# i2c-sensor-bridge.net
KiCad netlist of a schematic drawn in EAGLE
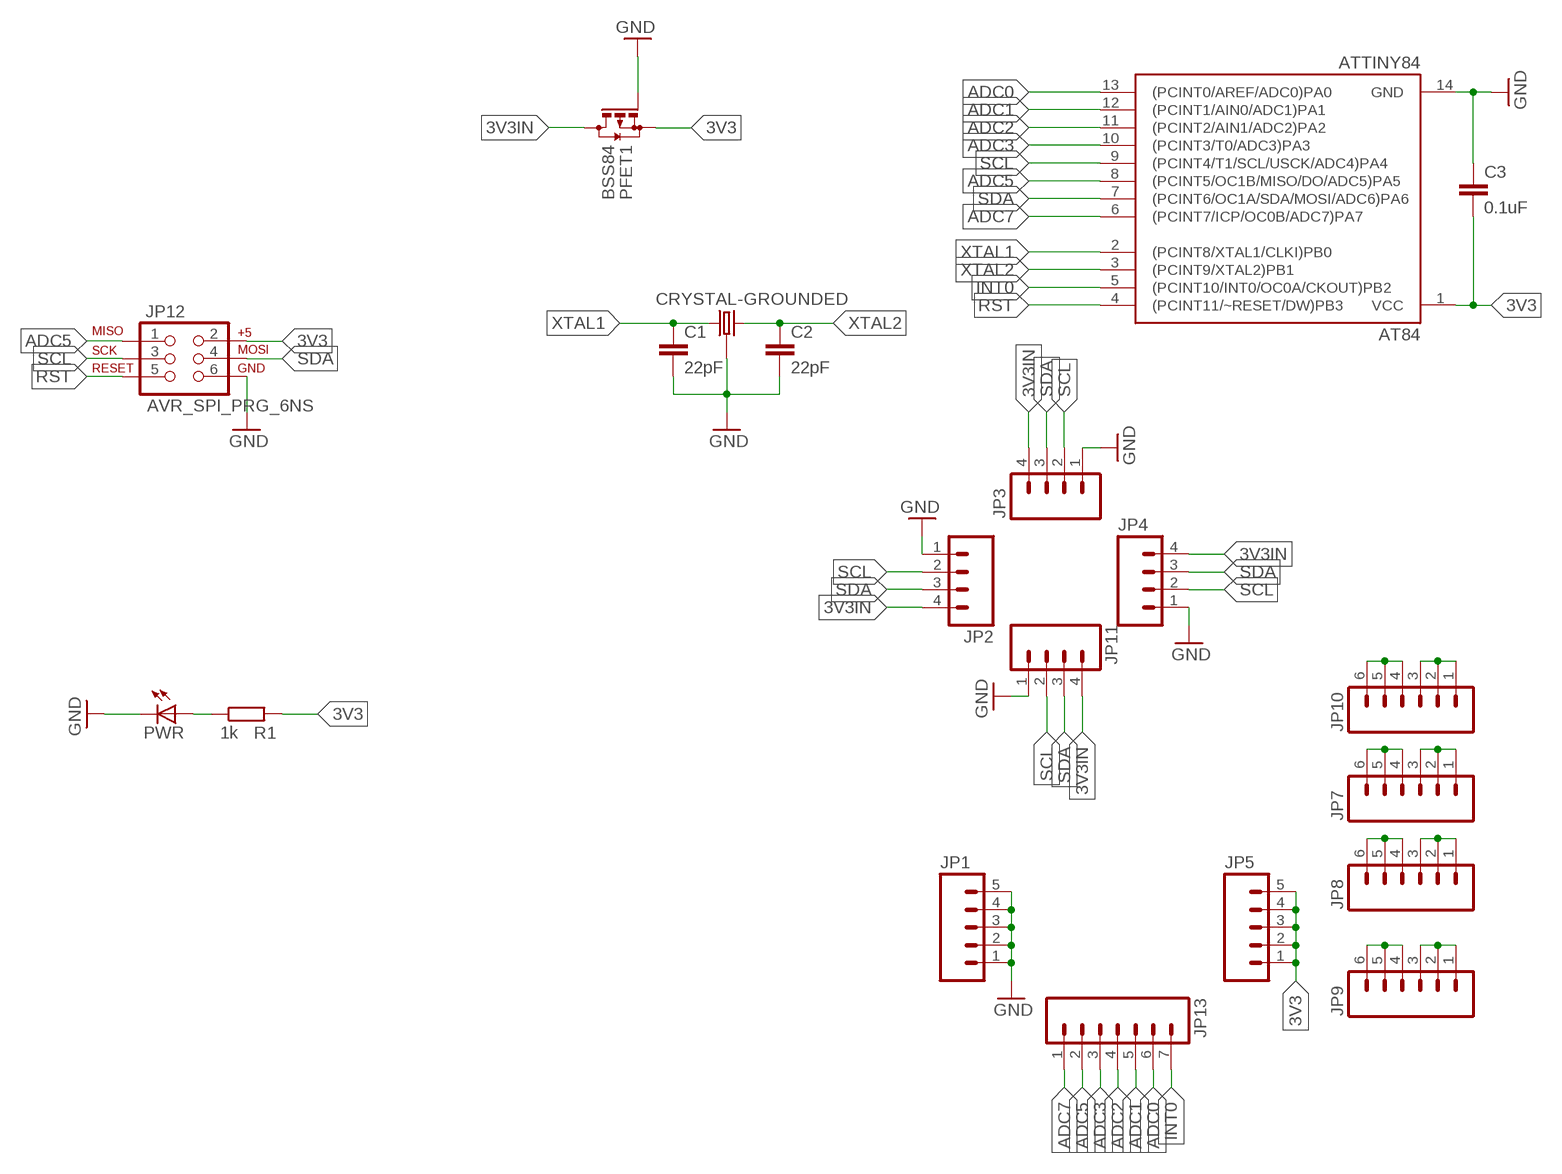
[diagram p0: schematic, sheet 1]

(export (version "E")
  (design (tool "Eeschema 10.0.6"))
  (components
    (comp (ref "AT84")
      (value "ATTINY84")
      (footprint "eagle-import:SO14")
      (libsource (lib "eagle-import") (part "ATTINY84"))
    )
    (comp (ref "C1")
      (value "22pF")
      (footprint "eagle-import:C0805")
      (libsource (lib "eagle-import") (part "C-EUC0805"))
    )
    (comp (ref "C2")
      (value "22pF")
      (footprint "eagle-import:C0805")
      (libsource (lib "eagle-import") (part "C-EUC0805"))
    )
    (comp (ref "C3")
      (value "0.1uF")
      (footprint "eagle-import:C0805")
      (libsource (lib "eagle-import") (part "C-EUC0805"))
    )
    (comp (ref "CRYSTAL")
      (value "CRYSTAL-GROUNDED")
      (footprint "eagle-import:CRYSTAL-SMD-5X3")
      (libsource (lib "eagle-import") (part "CRYSTAL-GROUNDED"))
    )
    (comp (ref "JP1")
      (value "M05LOCK")
      (footprint "eagle-import:1X05_LOCK")
      (libsource (lib "eagle-import") (part "M05LOCK"))
    )
    (comp (ref "JP2")
      (value "M04LOCK")
      (footprint "eagle-import:1X04_LOCK")
      (libsource (lib "eagle-import") (part "M04LOCK"))
    )
    (comp (ref "JP3")
      (value "M04LOCK")
      (footprint "eagle-import:1X04_LOCK")
      (libsource (lib "eagle-import") (part "M04LOCK"))
    )
    (comp (ref "JP4")
      (value "M04LOCK")
      (footprint "eagle-import:1X04_LOCK")
      (libsource (lib "eagle-import") (part "M04LOCK"))
    )
    (comp (ref "JP5")
      (value "M05LOCK")
      (footprint "eagle-import:1X05_LOCK")
      (libsource (lib "eagle-import") (part "M05LOCK"))
    )
    (comp (ref "JP7")
      (value "M06NO_SILK_FEMALE_PTH")
      (footprint "eagle-import:1X06_NO_SILK")
      (libsource (lib "eagle-import") (part "M06NO_SILK_FEMALE_PTH"))
    )
    (comp (ref "JP8")
      (value "M06NO_SILK_FEMALE_PTH")
      (footprint "eagle-import:1X06_NO_SILK")
      (libsource (lib "eagle-import") (part "M06NO_SILK_FEMALE_PTH"))
    )
    (comp (ref "JP9")
      (value "M06NO_SILK_FEMALE_PTH")
      (footprint "eagle-import:1X06_NO_SILK")
      (libsource (lib "eagle-import") (part "M06NO_SILK_FEMALE_PTH"))
    )
    (comp (ref "JP10")
      (value "M06NO_SILK_FEMALE_PTH")
      (footprint "eagle-import:1X06_NO_SILK")
      (libsource (lib "eagle-import") (part "M06NO_SILK_FEMALE_PTH"))
    )
    (comp (ref "JP11")
      (value "M04LOCK")
      (footprint "eagle-import:1X04_LOCK")
      (libsource (lib "eagle-import") (part "M04LOCK"))
    )
    (comp (ref "JP12")
      (value "AVR_SPI_PRG_6NS")
      (footprint "eagle-import:2X3-NS")
      (libsource (lib "eagle-import") (part "AVR_SPI_PRG_6NS"))
    )
    (comp (ref "JP13")
      (value "M07LOCK")
      (footprint "eagle-import:1X07_LOCK")
      (libsource (lib "eagle-import") (part "M07LOCK"))
    )
    (comp (ref "PFET1")
      (value "BSS84")
      (footprint "eagle-import:SOT23")
      (libsource (lib "eagle-import") (part "BSS84"))
    )
    (comp (ref "PWR")
      (value "LEDCHIPLED_0805")
      (footprint "eagle-import:CHIPLED_0805")
      (libsource (lib "eagle-import") (part "LEDCHIPLED_0805"))
    )
    (comp (ref "R1")
      (value "1k")
      (footprint "eagle-import:R0805")
      (libsource (lib "eagle-import") (part "R-EU_R0805"))
    )
  )
  (nets
    (net (code "1") (name "3V3") (class "Default")
      (node (ref "AT84") (pin "1") (pinfunction "VCC_1") (pintype "bidirectional"))
      (node (ref "C3") (pin "2") (pinfunction "2_2") (pintype "passive"))
      (node (ref "JP12") (pin "2") (pinfunction "2_2") (pintype "passive"))
      (node (ref "JP5") (pin "1") (pinfunction "1_1") (pintype "passive"))
      (node (ref "JP5") (pin "2") (pinfunction "2_2") (pintype "passive"))
      (node (ref "JP5") (pin "3") (pinfunction "3_3") (pintype "passive"))
      (node (ref "JP5") (pin "4") (pinfunction "4_4") (pintype "passive"))
      (node (ref "JP5") (pin "5") (pinfunction "5_5") (pintype "passive"))
      (node (ref "PFET1") (pin "2") (pinfunction "S_2") (pintype "passive"))
      (node (ref "R1") (pin "2") (pinfunction "2_2") (pintype "passive"))
    )
    (net (code "2") (name "3V3IN") (class "Default")
      (node (ref "JP11") (pin "4") (pinfunction "4_4") (pintype "passive"))
      (node (ref "JP2") (pin "4") (pinfunction "4_4") (pintype "passive"))
      (node (ref "JP3") (pin "4") (pinfunction "4_4") (pintype "passive"))
      (node (ref "JP4") (pin "4") (pinfunction "4_4") (pintype "passive"))
      (node (ref "PFET1") (pin "3") (pinfunction "D_3") (pintype "passive"))
    )
    (net (code "3") (name "ADC0") (class "Default")
      (node (ref "AT84") (pin "13") (pinfunction "(PCINT0/AREF/ADC0)PA0_13") (pintype "bidirectional"))
      (node (ref "JP13") (pin "6") (pinfunction "6_6") (pintype "passive"))
    )
    (net (code "4") (name "ADC1") (class "Default")
      (node (ref "AT84") (pin "12") (pinfunction "(PCINT1/AIN0/ADC1)PA1_12") (pintype "bidirectional"))
      (node (ref "JP13") (pin "5") (pinfunction "5_5") (pintype "passive"))
    )
    (net (code "5") (name "ADC2") (class "Default")
      (node (ref "AT84") (pin "11") (pinfunction "(PCINT2/AIN1/ADC2)PA2_11") (pintype "bidirectional"))
      (node (ref "JP13") (pin "4") (pinfunction "4_4") (pintype "passive"))
    )
    (net (code "6") (name "ADC3") (class "Default")
      (node (ref "AT84") (pin "10") (pinfunction "(PCINT3/T0/ADC3)PA3_10") (pintype "bidirectional"))
      (node (ref "JP13") (pin "3") (pinfunction "3_3") (pintype "passive"))
    )
    (net (code "7") (name "ADC5") (class "Default")
      (node (ref "AT84") (pin "8") (pinfunction "(PCINT5/OC1B/MISO/DO/ADC5)PA5_8") (pintype "bidirectional"))
      (node (ref "JP12") (pin "1") (pinfunction "1_1") (pintype "passive"))
      (node (ref "JP13") (pin "2") (pinfunction "2_2") (pintype "passive"))
    )
    (net (code "8") (name "ADC7") (class "Default")
      (node (ref "AT84") (pin "6") (pinfunction "(PCINT7/ICP/OC0B/ADC7)PA7_6") (pintype "bidirectional"))
      (node (ref "JP13") (pin "1") (pinfunction "1_1") (pintype "passive"))
    )
    (net (code "9") (name "GND") (class "Default")
      (node (ref "AT84") (pin "14") (pinfunction "GND_14") (pintype "bidirectional"))
      (node (ref "C1") (pin "2") (pinfunction "2_2") (pintype "passive"))
      (node (ref "C2") (pin "2") (pinfunction "2_2") (pintype "passive"))
      (node (ref "C3") (pin "1") (pinfunction "1_1") (pintype "passive"))
      (node (ref "CRYSTAL") (pin "2") (pinfunction "3_2") (pintype "passive"))
      (node (ref "CRYSTAL") (pin "4") (pinfunction "3_4") (pintype "passive"))
      (node (ref "JP1") (pin "1") (pinfunction "1_1") (pintype "passive"))
      (node (ref "JP1") (pin "2") (pinfunction "2_2") (pintype "passive"))
      (node (ref "JP1") (pin "3") (pinfunction "3_3") (pintype "passive"))
      (node (ref "JP1") (pin "4") (pinfunction "4_4") (pintype "passive"))
      (node (ref "JP1") (pin "5") (pinfunction "5_5") (pintype "passive"))
      (node (ref "JP11") (pin "1") (pinfunction "1_1") (pintype "passive"))
      (node (ref "JP12") (pin "6") (pinfunction "6_6") (pintype "passive"))
      (node (ref "JP2") (pin "1") (pinfunction "1_1") (pintype "passive"))
      (node (ref "JP3") (pin "1") (pinfunction "1_1") (pintype "passive"))
      (node (ref "JP4") (pin "1") (pinfunction "1_1") (pintype "passive"))
      (node (ref "PFET1") (pin "1") (pinfunction "G_1") (pintype "passive"))
      (node (ref "PWR") (pin "C") (pinfunction "C_C") (pintype "passive"))
    )
    (net (code "10") (name "INT0") (class "Default")
      (node (ref "AT84") (pin "5") (pinfunction "(PCINT10/INT0/OC0A/CKOUT)PB2_5") (pintype "bidirectional"))
      (node (ref "JP13") (pin "7") (pinfunction "7_7") (pintype "passive"))
    )
    (net (code "11") (name "Net-(JP7-Pad1)") (class "Default")
      (node (ref "JP7") (pin "1") (pinfunction "1_1") (pintype "passive"))
      (node (ref "JP7") (pin "2") (pinfunction "2_2") (pintype "passive"))
      (node (ref "JP7") (pin "3") (pinfunction "3_3") (pintype "passive"))
    )
    (net (code "12") (name "Net-(JP7-Pad4)") (class "Default")
      (node (ref "JP7") (pin "4") (pinfunction "4_4") (pintype "passive"))
      (node (ref "JP7") (pin "5") (pinfunction "5_5") (pintype "passive"))
      (node (ref "JP7") (pin "6") (pinfunction "6_6") (pintype "passive"))
    )
    (net (code "13") (name "Net-(JP8-Pad1)") (class "Default")
      (node (ref "JP8") (pin "1") (pinfunction "1_1") (pintype "passive"))
      (node (ref "JP8") (pin "2") (pinfunction "2_2") (pintype "passive"))
      (node (ref "JP8") (pin "3") (pinfunction "3_3") (pintype "passive"))
    )
    (net (code "14") (name "Net-(JP8-Pad4)") (class "Default")
      (node (ref "JP8") (pin "4") (pinfunction "4_4") (pintype "passive"))
      (node (ref "JP8") (pin "5") (pinfunction "5_5") (pintype "passive"))
      (node (ref "JP8") (pin "6") (pinfunction "6_6") (pintype "passive"))
    )
    (net (code "15") (name "Net-(JP9-Pad1)") (class "Default")
      (node (ref "JP9") (pin "1") (pinfunction "1_1") (pintype "passive"))
      (node (ref "JP9") (pin "2") (pinfunction "2_2") (pintype "passive"))
      (node (ref "JP9") (pin "3") (pinfunction "3_3") (pintype "passive"))
    )
    (net (code "16") (name "Net-(JP9-Pad4)") (class "Default")
      (node (ref "JP9") (pin "4") (pinfunction "4_4") (pintype "passive"))
      (node (ref "JP9") (pin "5") (pinfunction "5_5") (pintype "passive"))
      (node (ref "JP9") (pin "6") (pinfunction "6_6") (pintype "passive"))
    )
    (net (code "17") (name "Net-(JP10-Pad1)") (class "Default")
      (node (ref "JP10") (pin "1") (pinfunction "1_1") (pintype "passive"))
      (node (ref "JP10") (pin "2") (pinfunction "2_2") (pintype "passive"))
      (node (ref "JP10") (pin "3") (pinfunction "3_3") (pintype "passive"))
    )
    (net (code "18") (name "Net-(JP10-Pad4)") (class "Default")
      (node (ref "JP10") (pin "4") (pinfunction "4_4") (pintype "passive"))
      (node (ref "JP10") (pin "5") (pinfunction "5_5") (pintype "passive"))
      (node (ref "JP10") (pin "6") (pinfunction "6_6") (pintype "passive"))
    )
    (net (code "19") (name "Net-(PWR-PadA)") (class "Default")
      (node (ref "PWR") (pin "A") (pinfunction "A_A") (pintype "passive"))
      (node (ref "R1") (pin "1") (pinfunction "1_1") (pintype "passive"))
    )
    (net (code "20") (name "RST") (class "Default")
      (node (ref "AT84") (pin "4") (pinfunction "(PCINT11/~{RESET/DW})PB3_4") (pintype "bidirectional"))
      (node (ref "JP12") (pin "5") (pinfunction "5_5") (pintype "passive"))
    )
    (net (code "21") (name "SCL") (class "Default")
      (node (ref "AT84") (pin "9") (pinfunction "(PCINT4/T1/SCL/USCK/ADC4)PA4_9") (pintype "bidirectional"))
      (node (ref "JP11") (pin "2") (pinfunction "2_2") (pintype "passive"))
      (node (ref "JP12") (pin "3") (pinfunction "3_3") (pintype "passive"))
      (node (ref "JP2") (pin "2") (pinfunction "2_2") (pintype "passive"))
      (node (ref "JP3") (pin "2") (pinfunction "2_2") (pintype "passive"))
      (node (ref "JP4") (pin "2") (pinfunction "2_2") (pintype "passive"))
    )
    (net (code "22") (name "SDA") (class "Default")
      (node (ref "AT84") (pin "7") (pinfunction "(PCINT6/OC1A/SDA/MOSI/ADC6)PA6_7") (pintype "bidirectional"))
      (node (ref "JP11") (pin "3") (pinfunction "3_3") (pintype "passive"))
      (node (ref "JP12") (pin "4") (pinfunction "4_4") (pintype "passive"))
      (node (ref "JP2") (pin "3") (pinfunction "3_3") (pintype "passive"))
      (node (ref "JP3") (pin "3") (pinfunction "3_3") (pintype "passive"))
      (node (ref "JP4") (pin "3") (pinfunction "3_3") (pintype "passive"))
    )
    (net (code "23") (name "XTAL1") (class "Default")
      (node (ref "AT84") (pin "2") (pinfunction "(PCINT8/XTAL1/CLKI)PB0_2") (pintype "bidirectional"))
      (node (ref "C1") (pin "1") (pinfunction "1_1") (pintype "passive"))
      (node (ref "CRYSTAL") (pin "3") (pinfunction "1_3") (pintype "passive"))
    )
    (net (code "24") (name "XTAL2") (class "Default")
      (node (ref "AT84") (pin "3") (pinfunction "(PCINT9/XTAL2)PB1_3") (pintype "bidirectional"))
      (node (ref "C2") (pin "1") (pinfunction "1_1") (pintype "passive"))
      (node (ref "CRYSTAL") (pin "1") (pinfunction "2_1") (pintype "passive"))
    )
  )
)
